# 130902_AriloTX_REV2_0_0.net
KiCad netlist of a schematic drawn in EAGLE
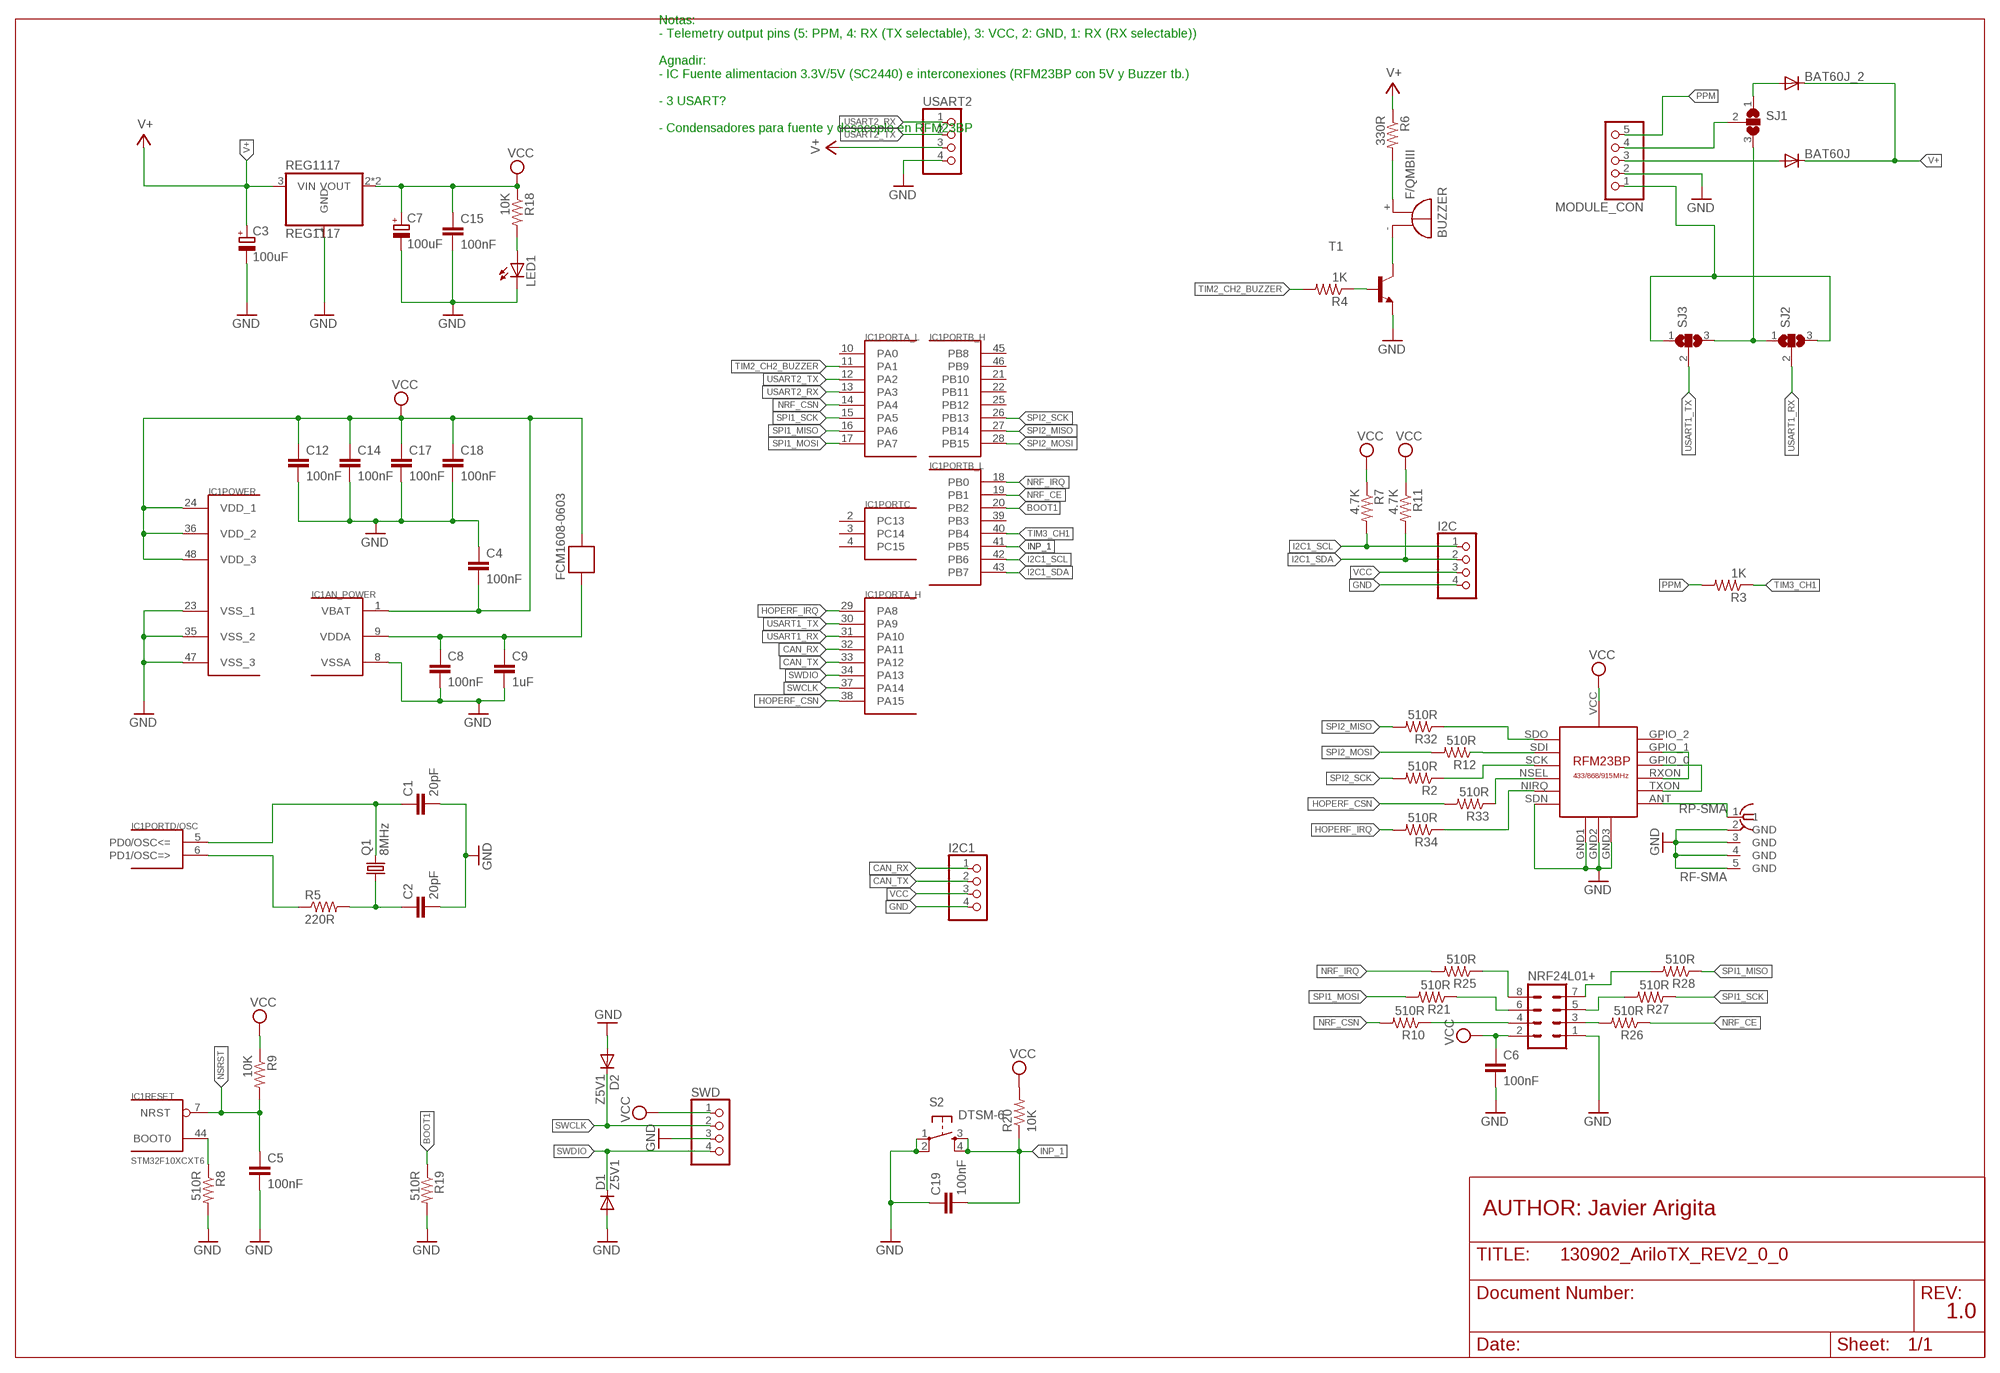
[diagram p0: schematic, sheet 1]

(export (version "E")
  (design (tool "Eeschema 10.0.6"))
  (components
    (comp (ref "BAT60J")
      (value "DIODE-SOD323-R")
      (footprint "eagle-import:SOD323-R")
      (libsource (lib "eagle-import") (part "DIODE-SOD323-R"))
    )
    (comp (ref "BAT60J_2")
      (value "DIODE-SOD323-R")
      (footprint "eagle-import:SOD323-R")
      (libsource (lib "eagle-import") (part "DIODE-SOD323-R"))
    )
    (comp (ref "BUZZER")
      (value "F/QMBIII")
      (footprint "eagle-import:F_QMBIII")
      (libsource (lib "eagle-import") (part "F/QMBIII"))
    )
    (comp (ref "C1")
      (value "20pF")
      (footprint "eagle-import:C0805")
      (libsource (lib "eagle-import") (part "C-EUC0805"))
    )
    (comp (ref "C2")
      (value "20pF")
      (footprint "eagle-import:C0805")
      (libsource (lib "eagle-import") (part "C-EUC0805"))
    )
    (comp (ref "C3")
      (value "100uF")
      (footprint "eagle-import:SMC_B")
      (libsource (lib "eagle-import") (part "CPOL-EUSMCB"))
    )
    (comp (ref "C4")
      (value "100nF")
      (footprint "eagle-import:C0805")
      (libsource (lib "eagle-import") (part "C-EUC0805"))
    )
    (comp (ref "C5")
      (value "100nF")
      (footprint "eagle-import:C0805")
      (libsource (lib "eagle-import") (part "C-EUC0805"))
    )
    (comp (ref "C6")
      (value "100nF")
      (footprint "eagle-import:C0805")
      (libsource (lib "eagle-import") (part "C-EUC0805"))
    )
    (comp (ref "C7")
      (value "100uF")
      (footprint "eagle-import:SMC_B")
      (libsource (lib "eagle-import") (part "CPOL-EUSMCB"))
    )
    (comp (ref "C8")
      (value "100nF")
      (footprint "eagle-import:C0805")
      (libsource (lib "eagle-import") (part "C-EUC0805"))
    )
    (comp (ref "C9")
      (value "1uF")
      (footprint "eagle-import:C3216")
      (libsource (lib "eagle-import") (part "resistor_C-EUC3216"))
    )
    (comp (ref "C12")
      (value "100nF")
      (footprint "eagle-import:C0805")
      (libsource (lib "eagle-import") (part "C-EUC0805"))
    )
    (comp (ref "C14")
      (value "100nF")
      (footprint "eagle-import:C0805")
      (libsource (lib "eagle-import") (part "C-EUC0805"))
    )
    (comp (ref "C15")
      (value "100nF")
      (footprint "eagle-import:C0805")
      (libsource (lib "eagle-import") (part "C-EUC0805"))
    )
    (comp (ref "C17")
      (value "100nF")
      (footprint "eagle-import:C0805")
      (libsource (lib "eagle-import") (part "C-EUC0805"))
    )
    (comp (ref "C18")
      (value "100nF")
      (footprint "eagle-import:C0805")
      (libsource (lib "eagle-import") (part "C-EUC0805"))
    )
    (comp (ref "C19")
      (value "100nF")
      (footprint "eagle-import:C0805")
      (libsource (lib "eagle-import") (part "C-EUC0805"))
    )
    (comp (ref "D1")
      (value "Z5V1")
      (footprint "eagle-import:SOD323-R")
      (libsource (lib "eagle-import") (part "DIODE-SOD323-R"))
    )
    (comp (ref "D2")
      (value "Z5V1")
      (footprint "eagle-import:SOD323-R")
      (libsource (lib "eagle-import") (part "DIODE-SOD323-R"))
    )
    (comp (ref "FCM1608-0603")
      (value "FERRITE-BEAD")
      (footprint "eagle-import:R0603")
      (libsource (lib "eagle-import") (part "FERRITE-BEAD"))
    )
    (comp (ref "I2C")
      (value "PINHD-1X4")
      (footprint "eagle-import:1X04")
      (libsource (lib "eagle-import") (part "PINHD-1X4"))
    )
    (comp (ref "I2C1")
      (value "PINHD-1X4")
      (footprint "eagle-import:1X04")
      (libsource (lib "eagle-import") (part "PINHD-1X4"))
    )
    (comp (ref "IC1")
      (value "STM32F10XCXT6")
      (footprint "eagle-import:TQFP48")
      (libsource (lib "eagle-import") (part "STM32F10XCXT6"))
    )
    (comp (ref "LED1")
      (value "LED0805")
      (footprint "eagle-import:CHIPLED_0805")
      (libsource (lib "eagle-import") (part "LED0805"))
    )
    (comp (ref "MODULE_CON")
      (value "PINHD-1X5")
      (footprint "eagle-import:1X05")
      (libsource (lib "eagle-import") (part "PINHD-1X5"))
    )
    (comp (ref "NRF24L01+")
      (value "MA04-2")
      (footprint "eagle-import:MA04-2")
      (libsource (lib "eagle-import") (part "MA04-2"))
    )
    (comp (ref "Q1")
      (value "8MHz")
      (footprint "eagle-import:SM49")
      (libsource (lib "eagle-import") (part "CRYSTALSM49"))
    )
    (comp (ref "R2")
      (value "510R")
      (footprint "eagle-import:R0805")
      (libsource (lib "eagle-import") (part "RESISTOR0805"))
    )
    (comp (ref "R3")
      (value "1K")
      (footprint "eagle-import:R0805")
      (libsource (lib "eagle-import") (part "RESISTOR0805"))
    )
    (comp (ref "R4")
      (value "1K")
      (footprint "eagle-import:R0805")
      (libsource (lib "eagle-import") (part "RESISTOR0805"))
    )
    (comp (ref "R5")
      (value "220R")
      (footprint "eagle-import:R0805")
      (libsource (lib "eagle-import") (part "RESISTOR0805"))
    )
    (comp (ref "R6")
      (value "330R")
      (footprint "eagle-import:R0805")
      (libsource (lib "eagle-import") (part "RESISTOR0805"))
    )
    (comp (ref "R7")
      (value "4.7K")
      (footprint "eagle-import:R0805")
      (libsource (lib "eagle-import") (part "RESISTOR0805"))
    )
    (comp (ref "R8")
      (value "510R")
      (footprint "eagle-import:R0805")
      (libsource (lib "eagle-import") (part "RESISTOR0805"))
    )
    (comp (ref "R9")
      (value "10K")
      (footprint "eagle-import:R0805")
      (libsource (lib "eagle-import") (part "RESISTOR0805"))
    )
    (comp (ref "R10")
      (value "510R")
      (footprint "eagle-import:R0805")
      (libsource (lib "eagle-import") (part "RESISTOR0805"))
    )
    (comp (ref "R11")
      (value "4.7K")
      (footprint "eagle-import:R0805")
      (libsource (lib "eagle-import") (part "RESISTOR0805"))
    )
    (comp (ref "R12")
      (value "510R")
      (footprint "eagle-import:R0805")
      (libsource (lib "eagle-import") (part "RESISTOR0805"))
    )
    (comp (ref "R18")
      (value "10K")
      (footprint "eagle-import:R0805")
      (libsource (lib "eagle-import") (part "RESISTOR0805"))
    )
    (comp (ref "R19")
      (value "510R")
      (footprint "eagle-import:R0805")
      (libsource (lib "eagle-import") (part "RESISTOR0805"))
    )
    (comp (ref "R20")
      (value "10K")
      (footprint "eagle-import:R0805")
      (libsource (lib "eagle-import") (part "RESISTOR0805"))
    )
    (comp (ref "R21")
      (value "510R")
      (footprint "eagle-import:R0805")
      (libsource (lib "eagle-import") (part "RESISTOR0805"))
    )
    (comp (ref "R25")
      (value "510R")
      (footprint "eagle-import:R0805")
      (libsource (lib "eagle-import") (part "RESISTOR0805"))
    )
    (comp (ref "R26")
      (value "510R")
      (footprint "eagle-import:R0805")
      (libsource (lib "eagle-import") (part "RESISTOR0805"))
    )
    (comp (ref "R27")
      (value "510R")
      (footprint "eagle-import:R0805")
      (libsource (lib "eagle-import") (part "RESISTOR0805"))
    )
    (comp (ref "R28")
      (value "510R")
      (footprint "eagle-import:R0805")
      (libsource (lib "eagle-import") (part "RESISTOR0805"))
    )
    (comp (ref "R32")
      (value "510R")
      (footprint "eagle-import:R0805")
      (libsource (lib "eagle-import") (part "RESISTOR0805"))
    )
    (comp (ref "R33")
      (value "510R")
      (footprint "eagle-import:R0805")
      (libsource (lib "eagle-import") (part "RESISTOR0805"))
    )
    (comp (ref "R34")
      (value "510R")
      (footprint "eagle-import:R0805")
      (libsource (lib "eagle-import") (part "RESISTOR0805"))
    )
    (comp (ref "REG1117")
      (value "REG1117")
      (footprint "eagle-import:SOT223")
      (libsource (lib "eagle-import") (part "REG1117"))
    )
    (comp (ref "RP-SMA")
      (value "RF-SMA")
      (footprint "eagle-import:BU-SMA-H")
      (libsource (lib "eagle-import") (part "RF-SMA"))
    )
    (comp (ref "S2")
      (value "DTSM-6")
      (footprint "eagle-import:DTSM-6")
      (libsource (lib "eagle-import") (part "DTSM-6"))
    )
    (comp (ref "SJ1")
      (value "SJ2W")
      (footprint "eagle-import:SJ_2")
      (libsource (lib "eagle-import") (part "SJ2W"))
    )
    (comp (ref "SJ2")
      (value "SJ2W")
      (footprint "eagle-import:SJ_2")
      (libsource (lib "eagle-import") (part "SJ2W"))
    )
    (comp (ref "SJ3")
      (value "SJ2W")
      (footprint "eagle-import:SJ_2")
      (libsource (lib "eagle-import") (part "SJ2W"))
    )
    (comp (ref "SWD")
      (value "PINHD-1X4")
      (footprint "eagle-import:1X04")
      (libsource (lib "eagle-import") (part "PINHD-1X4"))
    )
    (comp (ref "T1")
      (value "BC848-NPN-SOT23-BEC")
      (footprint "eagle-import:SOT23-BEC")
      (libsource (lib "eagle-import") (part "-NPN-SOT23-BECBC848"))
    )
    (comp (ref "U$1")
      (value "RFM23BP")
      (footprint "eagle-import:RFM23BP")
      (libsource (lib "eagle-import") (part "RFM23BP"))
    )
    (comp (ref "USART2")
      (value "PINHD-1X4")
      (footprint "eagle-import:1X04")
      (libsource (lib "eagle-import") (part "PINHD-1X4"))
    )
  )
  (nets
    (net (code "1") (name "BOOT1") (class "Default")
      (node (ref "IC1") (pin "20") (pinfunction "PB2_20") (pintype "bidirectional"))
      (node (ref "R19") (pin "1") (pinfunction "1_1") (pintype "passive"))
    )
    (net (code "2") (name "CAN_RX") (class "Default")
      (node (ref "I2C1") (pin "1") (pinfunction "1_1") (pintype "passive"))
      (node (ref "IC1") (pin "32") (pinfunction "PA11_32") (pintype "bidirectional"))
    )
    (net (code "3") (name "CAN_TX") (class "Default")
      (node (ref "I2C1") (pin "2") (pinfunction "2_2") (pintype "passive"))
      (node (ref "IC1") (pin "33") (pinfunction "PA12_33") (pintype "bidirectional"))
    )
    (net (code "4") (name "GND") (class "Default")
      (node (ref "C1") (pin "2") (pinfunction "2_2") (pintype "passive"))
      (node (ref "C12") (pin "2") (pinfunction "2_2") (pintype "passive"))
      (node (ref "C14") (pin "2") (pinfunction "2_2") (pintype "passive"))
      (node (ref "C15") (pin "2") (pinfunction "2_2") (pintype "passive"))
      (node (ref "C17") (pin "2") (pinfunction "2_2") (pintype "passive"))
      (node (ref "C18") (pin "2") (pinfunction "2_2") (pintype "passive"))
      (node (ref "C19") (pin "1") (pinfunction "1_1") (pintype "passive"))
      (node (ref "C2") (pin "2") (pinfunction "2_2") (pintype "passive"))
      (node (ref "C3") (pin "-") (pinfunction "-_-") (pintype "passive"))
      (node (ref "C4") (pin "1") (pinfunction "1_1") (pintype "passive"))
      (node (ref "C5") (pin "2") (pinfunction "2_2") (pintype "passive"))
      (node (ref "C6") (pin "2") (pinfunction "2_2") (pintype "passive"))
      (node (ref "C7") (pin "-") (pinfunction "-_-") (pintype "passive"))
      (node (ref "C8") (pin "2") (pinfunction "2_2") (pintype "passive"))
      (node (ref "C9") (pin "2") (pinfunction "2_2") (pintype "passive"))
      (node (ref "D1") (pin "A") (pinfunction "A_A") (pintype "passive"))
      (node (ref "D2") (pin "A") (pinfunction "A_A") (pintype "passive"))
      (node (ref "I2C") (pin "4") (pinfunction "4_4") (pintype "passive"))
      (node (ref "I2C1") (pin "4") (pinfunction "4_4") (pintype "passive"))
      (node (ref "IC1") (pin "23") (pinfunction "VSS_1_23") (pintype "power_in"))
      (node (ref "IC1") (pin "35") (pinfunction "VSS_2_35") (pintype "power_in"))
      (node (ref "IC1") (pin "47") (pinfunction "VSS_3_47") (pintype "power_in"))
      (node (ref "IC1") (pin "8") (pinfunction "VSSA_8") (pintype "power_in"))
      (node (ref "LED1") (pin "C") (pinfunction "C_C") (pintype "passive"))
      (node (ref "MODULE_CON") (pin "2") (pinfunction "2_2") (pintype "passive"))
      (node (ref "NRF24L01+") (pin "1") (pinfunction "1_1") (pintype "passive"))
      (node (ref "R19") (pin "2") (pinfunction "2_2") (pintype "passive"))
      (node (ref "R8") (pin "2") (pinfunction "2_2") (pintype "passive"))
      (node (ref "REG1117") (pin "1") (pinfunction "GND_1") (pintype "power_in"))
      (node (ref "RP-SMA") (pin "2") (pinfunction "GND_2") (pintype "power_in"))
      (node (ref "RP-SMA") (pin "3") (pinfunction "GND_3") (pintype "bidirectional"))
      (node (ref "RP-SMA") (pin "4") (pinfunction "GND_4") (pintype "bidirectional"))
      (node (ref "RP-SMA") (pin "5") (pinfunction "GND_5") (pintype "bidirectional"))
      (node (ref "S2") (pin "1") (pinfunction "1_1") (pintype "passive"))
      (node (ref "S2") (pin "2") (pinfunction "2_2") (pintype "passive"))
      (node (ref "SWD") (pin "3") (pinfunction "3_3") (pintype "passive"))
      (node (ref "T1") (pin "E") (pinfunction "E_E") (pintype "passive"))
      (node (ref "U$1") (pin "GND1") (pinfunction "GND1_GND1") (pintype "power_in"))
      (node (ref "U$1") (pin "GND2") (pinfunction "GND2_GND2") (pintype "power_in"))
      (node (ref "U$1") (pin "GND3") (pinfunction "GND3_GND3") (pintype "power_in"))
      (node (ref "U$1") (pin "SDN") (pinfunction "SDN_SDN") (pintype "bidirectional"))
      (node (ref "USART2") (pin "4") (pinfunction "4_4") (pintype "passive"))
    )
    (net (code "5") (name "HOPERF_CSN") (class "Default")
      (node (ref "IC1") (pin "38") (pinfunction "PA15_38") (pintype "bidirectional"))
      (node (ref "R33") (pin "2") (pinfunction "2_2") (pintype "passive"))
    )
    (net (code "6") (name "HOPERF_IRQ") (class "Default")
      (node (ref "IC1") (pin "29") (pinfunction "PA8_29") (pintype "bidirectional"))
      (node (ref "R34") (pin "2") (pinfunction "2_2") (pintype "passive"))
    )
    (net (code "7") (name "I2C1_SCL") (class "Default")
      (node (ref "I2C") (pin "1") (pinfunction "1_1") (pintype "passive"))
      (node (ref "IC1") (pin "42") (pinfunction "PB6_42") (pintype "bidirectional"))
      (node (ref "R7") (pin "2") (pinfunction "2_2") (pintype "passive"))
    )
    (net (code "8") (name "I2C1_SDA") (class "Default")
      (node (ref "I2C") (pin "2") (pinfunction "2_2") (pintype "passive"))
      (node (ref "IC1") (pin "43") (pinfunction "PB7_43") (pintype "bidirectional"))
      (node (ref "R11") (pin "2") (pinfunction "2_2") (pintype "passive"))
    )
    (net (code "9") (name "INP_1") (class "Default")
      (node (ref "C19") (pin "2") (pinfunction "2_2") (pintype "passive"))
      (node (ref "IC1") (pin "41") (pinfunction "PB5_41") (pintype "bidirectional"))
      (node (ref "R20") (pin "1") (pinfunction "1_1") (pintype "passive"))
      (node (ref "S2") (pin "3") (pinfunction "3_3") (pintype "passive"))
      (node (ref "S2") (pin "4") (pinfunction "4_4") (pintype "passive"))
    )
    (net (code "10") (name "NRF_CE") (class "Default")
      (node (ref "IC1") (pin "19") (pinfunction "PB1_19") (pintype "bidirectional"))
      (node (ref "R26") (pin "1") (pinfunction "1_1") (pintype "passive"))
    )
    (net (code "11") (name "NRF_CSN") (class "Default")
      (node (ref "IC1") (pin "14") (pinfunction "PA4_14") (pintype "bidirectional"))
      (node (ref "R10") (pin "2") (pinfunction "2_2") (pintype "passive"))
    )
    (net (code "12") (name "NRF_IRQ") (class "Default")
      (node (ref "IC1") (pin "18") (pinfunction "PB0_18") (pintype "bidirectional"))
      (node (ref "R25") (pin "2") (pinfunction "2_2") (pintype "passive"))
    )
    (net (code "13") (name "NSRST") (class "Default")
      (node (ref "C5") (pin "1") (pinfunction "1_1") (pintype "passive"))
      (node (ref "IC1") (pin "7") (pinfunction "NRST_7") (pintype "input"))
      (node (ref "R9") (pin "2") (pinfunction "2_2") (pintype "passive"))
    )
    (net (code "14") (name "Net-(BAT60J-PadA)") (class "Default")
      (node (ref "BAT60J") (pin "A") (pinfunction "A_A") (pintype "passive"))
      (node (ref "MODULE_CON") (pin "3") (pinfunction "3_3") (pintype "passive"))
    )
    (net (code "15") (name "Net-(BAT60J_2-PadA)") (class "Default")
      (node (ref "BAT60J_2") (pin "A") (pinfunction "A_A") (pintype "passive"))
      (node (ref "SJ1") (pin "1") (pinfunction "1_1") (pintype "passive"))
    )
    (net (code "16") (name "Net-(BUZZER-+)") (class "Default")
      (node (ref "BUZZER") (pin "-") (pinfunction "+_-") (pintype "passive"))
      (node (ref "T1") (pin "C") (pinfunction "C_C") (pintype "passive"))
    )
    (net (code "17") (name "Net-(BUZZER--)") (class "Default")
      (node (ref "BUZZER") (pin "+") (pinfunction "-_+") (pintype "passive"))
      (node (ref "R6") (pin "2") (pinfunction "2_2") (pintype "passive"))
    )
    (net (code "18") (name "Net-(C2-Pad1)") (class "Default")
      (node (ref "C2") (pin "1") (pinfunction "1_1") (pintype "passive"))
      (node (ref "Q1") (pin "1") (pinfunction "1_1") (pintype "passive"))
      (node (ref "R5") (pin "2") (pinfunction "2_2") (pintype "passive"))
    )
    (net (code "19") (name "Net-(FCM1608-0603-P$2)") (class "Default")
      (node (ref "C8") (pin "1") (pinfunction "1_1") (pintype "passive"))
      (node (ref "C9") (pin "1") (pinfunction "1_1") (pintype "passive"))
      (node (ref "FCM1608-0603") (pin "2") (pinfunction "P$2_2") (pintype "bidirectional"))
      (node (ref "IC1") (pin "9") (pinfunction "VDDA_9") (pintype "power_in"))
    )
    (net (code "20") (name "Net-(IC1G-PD0{slash}OSC<=)") (class "Default")
      (node (ref "C1") (pin "1") (pinfunction "1_1") (pintype "passive"))
      (node (ref "IC1") (pin "5") (pinfunction "PD0/OSC<=_5") (pintype "bidirectional"))
      (node (ref "Q1") (pin "2") (pinfunction "2_2") (pintype "passive"))
    )
    (net (code "21") (name "Net-(IC1G-PD1{slash}OSC=>)") (class "Default")
      (node (ref "IC1") (pin "6") (pinfunction "PD1/OSC=>_6") (pintype "bidirectional"))
      (node (ref "R5") (pin "1") (pinfunction "1_1") (pintype "passive"))
    )
    (net (code "22") (name "Net-(IC1I-BOOT0)") (class "Default")
      (node (ref "IC1") (pin "44") (pinfunction "BOOT0_44") (pintype "input"))
      (node (ref "R8") (pin "1") (pinfunction "1_1") (pintype "passive"))
    )
    (net (code "23") (name "Net-(LED1-PadA)") (class "Default")
      (node (ref "LED1") (pin "A") (pinfunction "A_A") (pintype "passive"))
      (node (ref "R18") (pin "2") (pinfunction "2_2") (pintype "passive"))
    )
    (net (code "24") (name "Net-(MODULE_CON-Pad1)") (class "Default")
      (node (ref "MODULE_CON") (pin "1") (pinfunction "1_1") (pintype "passive"))
      (node (ref "SJ2") (pin "3") (pinfunction "3_3") (pintype "passive"))
      (node (ref "SJ3") (pin "1") (pinfunction "1_1") (pintype "passive"))
    )
    (net (code "25") (name "Net-(MODULE_CON-Pad4)") (class "Default")
      (node (ref "MODULE_CON") (pin "4") (pinfunction "4_4") (pintype "passive"))
      (node (ref "SJ1") (pin "2") (pinfunction "2_2") (pintype "passive"))
    )
    (net (code "26") (name "Net-(NRF24L01+-Pad3)") (class "Default")
      (node (ref "NRF24L01+") (pin "3") (pinfunction "3_3") (pintype "passive"))
      (node (ref "R26") (pin "2") (pinfunction "2_2") (pintype "passive"))
    )
    (net (code "27") (name "Net-(NRF24L01+-Pad4)") (class "Default")
      (node (ref "NRF24L01+") (pin "4") (pinfunction "4_4") (pintype "passive"))
      (node (ref "R10") (pin "1") (pinfunction "1_1") (pintype "passive"))
    )
    (net (code "28") (name "Net-(NRF24L01+-Pad5)") (class "Default")
      (node (ref "NRF24L01+") (pin "5") (pinfunction "5_5") (pintype "passive"))
      (node (ref "R27") (pin "2") (pinfunction "2_2") (pintype "passive"))
    )
    (net (code "29") (name "Net-(NRF24L01+-Pad6)") (class "Default")
      (node (ref "NRF24L01+") (pin "6") (pinfunction "6_6") (pintype "passive"))
      (node (ref "R21") (pin "1") (pinfunction "1_1") (pintype "passive"))
    )
    (net (code "30") (name "Net-(NRF24L01+-Pad7)") (class "Default")
      (node (ref "NRF24L01+") (pin "7") (pinfunction "7_7") (pintype "passive"))
      (node (ref "R28") (pin "2") (pinfunction "2_2") (pintype "passive"))
    )
    (net (code "31") (name "Net-(NRF24L01+-Pad8)") (class "Default")
      (node (ref "NRF24L01+") (pin "8") (pinfunction "8_8") (pintype "passive"))
      (node (ref "R25") (pin "1") (pinfunction "1_1") (pintype "passive"))
    )
    (net (code "32") (name "Net-(R2-Pad1)") (class "Default")
      (node (ref "R2") (pin "1") (pinfunction "1_1") (pintype "passive"))
      (node (ref "U$1") (pin "SCK") (pinfunction "SCK_SCK") (pintype "bidirectional"))
    )
    (net (code "33") (name "Net-(R4-Pad1)") (class "Default")
      (node (ref "R4") (pin "1") (pinfunction "1_1") (pintype "passive"))
      (node (ref "T1") (pin "B") (pinfunction "B_B") (pintype "passive"))
    )
    (net (code "34") (name "Net-(R12-Pad1)") (class "Default")
      (node (ref "R12") (pin "1") (pinfunction "1_1") (pintype "passive"))
      (node (ref "U$1") (pin "SDI") (pinfunction "SDI_SDI") (pintype "bidirectional"))
    )
    (net (code "35") (name "Net-(R32-Pad1)") (class "Default")
      (node (ref "R32") (pin "1") (pinfunction "1_1") (pintype "passive"))
      (node (ref "U$1") (pin "SDO") (pinfunction "SDO_SDO") (pintype "bidirectional"))
    )
    (net (code "36") (name "Net-(R33-Pad1)") (class "Default")
      (node (ref "R33") (pin "1") (pinfunction "1_1") (pintype "passive"))
      (node (ref "U$1") (pin "NSEL") (pinfunction "NSEL_NSEL") (pintype "bidirectional"))
    )
    (net (code "37") (name "Net-(R34-Pad1)") (class "Default")
      (node (ref "R34") (pin "1") (pinfunction "1_1") (pintype "passive"))
      (node (ref "U$1") (pin "NIRQ") (pinfunction "NIRQ_NIRQ") (pintype "bidirectional"))
    )
    (net (code "38") (name "Net-(RP-SMA-Pad1)") (class "Default")
      (node (ref "RP-SMA") (pin "1") (pinfunction "1_1") (pintype "passive"))
      (node (ref "U$1") (pin "ANT") (pinfunction "ANT_ANT") (pintype "bidirectional"))
    )
    (net (code "39") (name "Net-(SJ1-Pad3)") (class "Default")
      (node (ref "SJ1") (pin "3") (pinfunction "3_3") (pintype "passive"))
      (node (ref "SJ2") (pin "1") (pinfunction "1_1") (pintype "passive"))
      (node (ref "SJ3") (pin "3") (pinfunction "3_3") (pintype "passive"))
    )
    (net (code "40") (name "Net-(U$1-PadGPIO_0)") (class "Default")
      (node (ref "U$1") (pin "GPIO_0") (pinfunction "GPIO_0_GPIO_0") (pintype "bidirectional"))
      (node (ref "U$1") (pin "TXON") (pinfunction "TXON_TXON") (pintype "bidirectional"))
    )
    (net (code "41") (name "Net-(U$1-PadGPIO_1)") (class "Default")
      (node (ref "U$1") (pin "GPIO_1") (pinfunction "GPIO_1_GPIO_1") (pintype "bidirectional"))
      (node (ref "U$1") (pin "RXON") (pinfunction "RXON_RXON") (pintype "bidirectional"))
    )
    (net (code "42") (name "PPM") (class "Default")
      (node (ref "MODULE_CON") (pin "5") (pinfunction "5_5") (pintype "passive"))
      (node (ref "R3") (pin "2") (pinfunction "2_2") (pintype "passive"))
    )
    (net (code "43") (name "SPI1_MISO") (class "Default")
      (node (ref "IC1") (pin "16") (pinfunction "PA6_16") (pintype "bidirectional"))
      (node (ref "R28") (pin "1") (pinfunction "1_1") (pintype "passive"))
    )
    (net (code "44") (name "SPI1_MOSI") (class "Default")
      (node (ref "IC1") (pin "17") (pinfunction "PA7_17") (pintype "bidirectional"))
      (node (ref "R21") (pin "2") (pinfunction "2_2") (pintype "passive"))
    )
    (net (code "45") (name "SPI1_SCK") (class "Default")
      (node (ref "IC1") (pin "15") (pinfunction "PA5_15") (pintype "bidirectional"))
      (node (ref "R27") (pin "1") (pinfunction "1_1") (pintype "passive"))
    )
    (net (code "46") (name "SPI2_MISO") (class "Default")
      (node (ref "IC1") (pin "27") (pinfunction "PB14_27") (pintype "bidirectional"))
      (node (ref "R32") (pin "2") (pinfunction "2_2") (pintype "passive"))
    )
    (net (code "47") (name "SPI2_MOSI") (class "Default")
      (node (ref "IC1") (pin "28") (pinfunction "PB15_28") (pintype "bidirectional"))
      (node (ref "R12") (pin "2") (pinfunction "2_2") (pintype "passive"))
    )
    (net (code "48") (name "SPI2_SCK") (class "Default")
      (node (ref "IC1") (pin "26") (pinfunction "PB13_26") (pintype "bidirectional"))
      (node (ref "R2") (pin "2") (pinfunction "2_2") (pintype "passive"))
    )
    (net (code "49") (name "SWCLK") (class "Default")
      (node (ref "D2") (pin "C") (pinfunction "C_C") (pintype "passive"))
      (node (ref "IC1") (pin "37") (pinfunction "PA14_37") (pintype "bidirectional"))
      (node (ref "SWD") (pin "2") (pinfunction "2_2") (pintype "passive"))
    )
    (net (code "50") (name "SWDIO") (class "Default")
      (node (ref "D1") (pin "C") (pinfunction "C_C") (pintype "passive"))
      (node (ref "IC1") (pin "34") (pinfunction "PA13_34") (pintype "bidirectional"))
      (node (ref "SWD") (pin "4") (pinfunction "4_4") (pintype "passive"))
    )
    (net (code "51") (name "TIM2_CH2_BUZZER") (class "Default")
      (node (ref "IC1") (pin "11") (pinfunction "PA1_11") (pintype "bidirectional"))
      (node (ref "R4") (pin "2") (pinfunction "2_2") (pintype "passive"))
    )
    (net (code "52") (name "TIM3_CH1") (class "Default")
      (node (ref "IC1") (pin "40") (pinfunction "PB4_40") (pintype "bidirectional"))
      (node (ref "R3") (pin "1") (pinfunction "1_1") (pintype "passive"))
    )
    (net (code "53") (name "USART1_RX") (class "Default")
      (node (ref "IC1") (pin "31") (pinfunction "PA10_31") (pintype "bidirectional"))
      (node (ref "SJ2") (pin "2") (pinfunction "2_2") (pintype "passive"))
    )
    (net (code "54") (name "USART1_TX") (class "Default")
      (node (ref "IC1") (pin "30") (pinfunction "PA9_30") (pintype "bidirectional"))
      (node (ref "SJ3") (pin "2") (pinfunction "2_2") (pintype "passive"))
    )
    (net (code "55") (name "USART2_RX") (class "Default")
      (node (ref "IC1") (pin "13") (pinfunction "PA3_13") (pintype "bidirectional"))
      (node (ref "USART2") (pin "1") (pinfunction "1_1") (pintype "passive"))
    )
    (net (code "56") (name "USART2_TX") (class "Default")
      (node (ref "IC1") (pin "12") (pinfunction "PA2_12") (pintype "bidirectional"))
      (node (ref "USART2") (pin "2") (pinfunction "2_2") (pintype "passive"))
    )
    (net (code "57") (name "V+") (class "Default")
      (node (ref "BAT60J") (pin "C") (pinfunction "C_C") (pintype "passive"))
      (node (ref "BAT60J_2") (pin "C") (pinfunction "C_C") (pintype "passive"))
      (node (ref "C3") (pin "+") (pinfunction "+_+") (pintype "passive"))
      (node (ref "R6") (pin "1") (pinfunction "1_1") (pintype "passive"))
      (node (ref "REG1117") (pin "3") (pinfunction "VIN_3") (pintype "input"))
      (node (ref "USART2") (pin "3") (pinfunction "3_3") (pintype "passive"))
    )
    (net (code "58") (name "VCC") (class "Default")
      (node (ref "C12") (pin "1") (pinfunction "1_1") (pintype "passive"))
      (node (ref "C14") (pin "1") (pinfunction "1_1") (pintype "passive"))
      (node (ref "C15") (pin "1") (pinfunction "1_1") (pintype "passive"))
      (node (ref "C17") (pin "1") (pinfunction "1_1") (pintype "passive"))
      (node (ref "C18") (pin "1") (pinfunction "1_1") (pintype "passive"))
      (node (ref "C4") (pin "2") (pinfunction "2_2") (pintype "passive"))
      (node (ref "C6") (pin "1") (pinfunction "1_1") (pintype "passive"))
      (node (ref "C7") (pin "+") (pinfunction "+_+") (pintype "passive"))
      (node (ref "FCM1608-0603") (pin "1") (pinfunction "P$1_1") (pintype "bidirectional"))
      (node (ref "I2C") (pin "3") (pinfunction "3_3") (pintype "passive"))
      (node (ref "I2C1") (pin "3") (pinfunction "3_3") (pintype "passive"))
      (node (ref "IC1") (pin "1") (pinfunction "VBAT_1") (pintype "power_in"))
      (node (ref "IC1") (pin "24") (pinfunction "VDD_1_24") (pintype "power_in"))
      (node (ref "IC1") (pin "36") (pinfunction "VDD_2_36") (pintype "power_in"))
      (node (ref "IC1") (pin "48") (pinfunction "VDD_3_48") (pintype "power_in"))
      (node (ref "NRF24L01+") (pin "2") (pinfunction "2_2") (pintype "passive"))
      (node (ref "R11") (pin "1") (pinfunction "1_1") (pintype "passive"))
      (node (ref "R18") (pin "1") (pinfunction "1_1") (pintype "passive"))
      (node (ref "R20") (pin "2") (pinfunction "2_2") (pintype "passive"))
      (node (ref "R7") (pin "1") (pinfunction "1_1") (pintype "passive"))
      (node (ref "R9") (pin "1") (pinfunction "1_1") (pintype "passive"))
      (node (ref "REG1117") (pin "2") (pinfunction "VOUT_2") (pintype "power_in"))
      (node (ref "REG1117") (pin "4") (pinfunction "VOUT_4") (pintype "power_in"))
      (node (ref "SWD") (pin "1") (pinfunction "1_1") (pintype "passive"))
      (node (ref "U$1") (pin "VCC") (pinfunction "VCC_VCC") (pintype "power_in"))
    )
    (net (code "59") (name "unconnected-(IC1C-PA0-Pad10)") (class "Default")
      (node (ref "IC1") (pin "10") (pinfunction "PA0_10") (pintype "bidirectional"))
    )
    (net (code "60") (name "unconnected-(IC1D-PB8-Pad45)") (class "Default")
      (node (ref "IC1") (pin "45") (pinfunction "PB8_45") (pintype "bidirectional"))
    )
    (net (code "61") (name "unconnected-(IC1D-PB9-Pad46)") (class "Default")
      (node (ref "IC1") (pin "46") (pinfunction "PB9_46") (pintype "bidirectional"))
    )
    (net (code "62") (name "unconnected-(IC1D-PB10-Pad21)") (class "Default")
      (node (ref "IC1") (pin "21") (pinfunction "PB10_21") (pintype "bidirectional"))
    )
    (net (code "63") (name "unconnected-(IC1D-PB11-Pad22)") (class "Default")
      (node (ref "IC1") (pin "22") (pinfunction "PB11_22") (pintype "bidirectional"))
    )
    (net (code "64") (name "unconnected-(IC1D-PB12-Pad25)") (class "Default")
      (node (ref "IC1") (pin "25") (pinfunction "PB12_25") (pintype "bidirectional"))
    )
    (net (code "65") (name "unconnected-(IC1E-PB3-Pad39)") (class "Default")
      (node (ref "IC1") (pin "39") (pinfunction "PB3_39") (pintype "bidirectional"))
    )
    (net (code "66") (name "unconnected-(IC1F-PC13-Pad2)") (class "Default")
      (node (ref "IC1") (pin "2") (pinfunction "PC13_2") (pintype "bidirectional"))
    )
    (net (code "67") (name "unconnected-(IC1F-PC14-Pad3)") (class "Default")
      (node (ref "IC1") (pin "3") (pinfunction "PC14_3") (pintype "bidirectional"))
    )
    (net (code "68") (name "unconnected-(IC1F-PC15-Pad4)") (class "Default")
      (node (ref "IC1") (pin "4") (pinfunction "PC15_4") (pintype "bidirectional"))
    )
    (net (code "69") (name "unconnected-(U$1-PadGPIO_2)") (class "Default")
      (node (ref "U$1") (pin "GPIO_2") (pinfunction "GPIO_2_GPIO_2") (pintype "bidirectional"))
    )
  )
)
